# Flow_sensor.net
KiCad netlist of a schematic drawn in Altium Designer
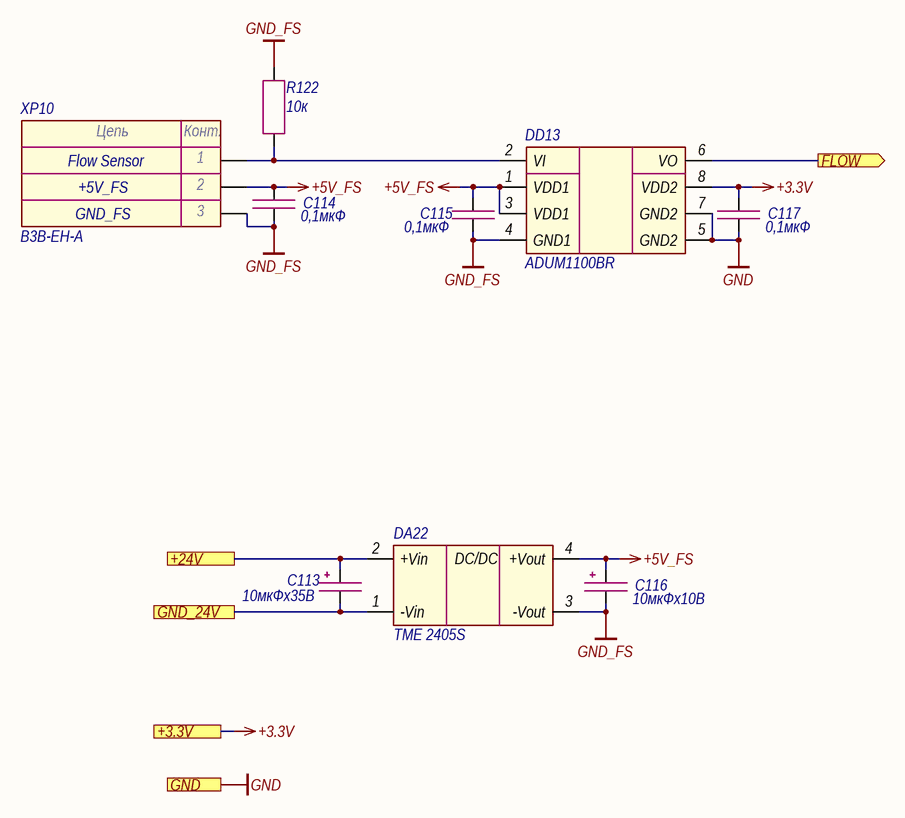
[diagram p0: Flow_sensor.SchDoc]

(export (version "E")
  (design (tool "Eeschema 10.0.6"))
  (components
    (comp (ref "C113")
      (value "10мкФх35B")
      (footprint "Pcb_library:CAP_C")
      (libsource (lib "Schem_library") (part "Capacitor_Polar"))
    )
    (comp (ref "C114")
      (value "0,1мкФ")
      (footprint "Pcb_library:CAP_0603")
      (fields (field (name "MANUFACTURER") "Murata"))
      (libsource (lib "Schem_library") (part "Capacitor"))
    )
    (comp (ref "C115")
      (value "0,1мкФ")
      (footprint "Pcb_library:CAP_0603")
      (fields (field (name "MANUFACTURER") "Murata"))
      (libsource (lib "Schem_library") (part "Capacitor"))
    )
    (comp (ref "C116")
      (value "10мкФх10B")
      (footprint "Pcb_library:CAP_A")
      (libsource (lib "Schem_library") (part "Capacitor_Polar"))
    )
    (comp (ref "C117")
      (value "0,1мкФ")
      (footprint "Pcb_library:CAP_0603")
      (fields (field (name "MANUFACTURER") "Murata"))
      (libsource (lib "Schem_library") (part "Capacitor"))
    )
    (comp (ref "DA22")
      (value "TME 2405S")
      (footprint "Pcb_library:TME (SIP-4)")
      (fields (field (name "MANUFACTURER") "Traco Power"))
      (libsource (lib "Schem_library") (part "TME"))
    )
    (comp (ref "DD13")
      (value "ADUM1100BR")
      (footprint "Pcb_library:SOIC-8")
      (fields (field (name "MANUFACTURER") "Analog Devices"))
      (libsource (lib "Schem_library") (part "ADUM1100"))
    )
    (comp (ref "R122")
      (value "10к")
      (footprint "Pcb_library:RES_0603")
      (fields (field (name "MANUFACTURER") "Yageo"))
      (libsource (lib "Schem_library") (part "Resistor"))
    )
    (comp (ref "XP10")
      (value "B3B-EH-A")
      (footprint "B3B-EH-A")
      (fields (field (name "MANUFACTURER") "JST"))
      (libsource (lib "Schem_library") (part "Connector-3"))
    )
  )
  (nets
    (net (code "1") (name "+3.3V") (class "Default")
      (node (ref "C117") (pin "1") (pinfunction "1_1") (pintype "passive"))
      (node (ref "DD13") (pin "8") (pinfunction "VDD2_8") (pintype "passive"))
    )
    (net (code "2") (name "+5V_FS") (class "Default")
      (node (ref "C114") (pin "1") (pinfunction "1_1") (pintype "passive"))
      (node (ref "C115") (pin "1") (pinfunction "1_1") (pintype "passive"))
      (node (ref "C116") (pin "1") (pinfunction "1_1") (pintype "passive"))
      (node (ref "DA22") (pin "4") (pinfunction "+Vout_4") (pintype "passive"))
      (node (ref "DD13") (pin "1") (pinfunction "VDD1_1") (pintype "passive"))
      (node (ref "DD13") (pin "3") (pinfunction "VDD1_3") (pintype "passive"))
      (node (ref "XP10") (pin "2") (pintype "passive"))
    )
    (net (code "3") (name "/+24V") (class "Default")
      (node (ref "C113") (pin "1") (pinfunction "1_1") (pintype "passive"))
      (node (ref "DA22") (pin "2") (pinfunction "+Vin_2") (pintype "passive"))
    )
    (net (code "4") (name "/FLOW") (class "Default")
      (node (ref "DD13") (pin "6") (pinfunction "VO_6") (pintype "passive"))
    )
    (net (code "5") (name "/GND_24V") (class "Default")
      (node (ref "C113") (pin "2") (pinfunction "2_2") (pintype "passive"))
      (node (ref "DA22") (pin "1") (pinfunction "-Vin_1") (pintype "passive"))
    )
    (net (code "6") (name "GND") (class "Default")
      (node (ref "C117") (pin "2") (pinfunction "2_2") (pintype "passive"))
      (node (ref "DD13") (pin "5") (pinfunction "GND2_5") (pintype "passive"))
      (node (ref "DD13") (pin "7") (pinfunction "GND2_7") (pintype "passive"))
    )
    (net (code "7") (name "GND_FS") (class "Default")
      (node (ref "C114") (pin "2") (pinfunction "2_2") (pintype "passive"))
      (node (ref "C115") (pin "2") (pinfunction "2_2") (pintype "passive"))
      (node (ref "C116") (pin "2") (pinfunction "2_2") (pintype "passive"))
      (node (ref "DA22") (pin "3") (pinfunction "-Vout_3") (pintype "passive"))
      (node (ref "DD13") (pin "4") (pinfunction "GND1_4") (pintype "passive"))
      (node (ref "R122") (pin "2") (pinfunction "2_2") (pintype "passive"))
      (node (ref "XP10") (pin "3") (pintype "passive"))
    )
    (net (code "8") (name "Net-(DD13-VI)") (class "Default")
      (node (ref "DD13") (pin "2") (pinfunction "VI_2") (pintype "passive"))
      (node (ref "R122") (pin "1") (pinfunction "1_1") (pintype "passive"))
      (node (ref "XP10") (pin "1") (pintype "passive"))
    )
  )
)
